# com_board.net
KiCad netlist of a schematic drawn in EAGLE
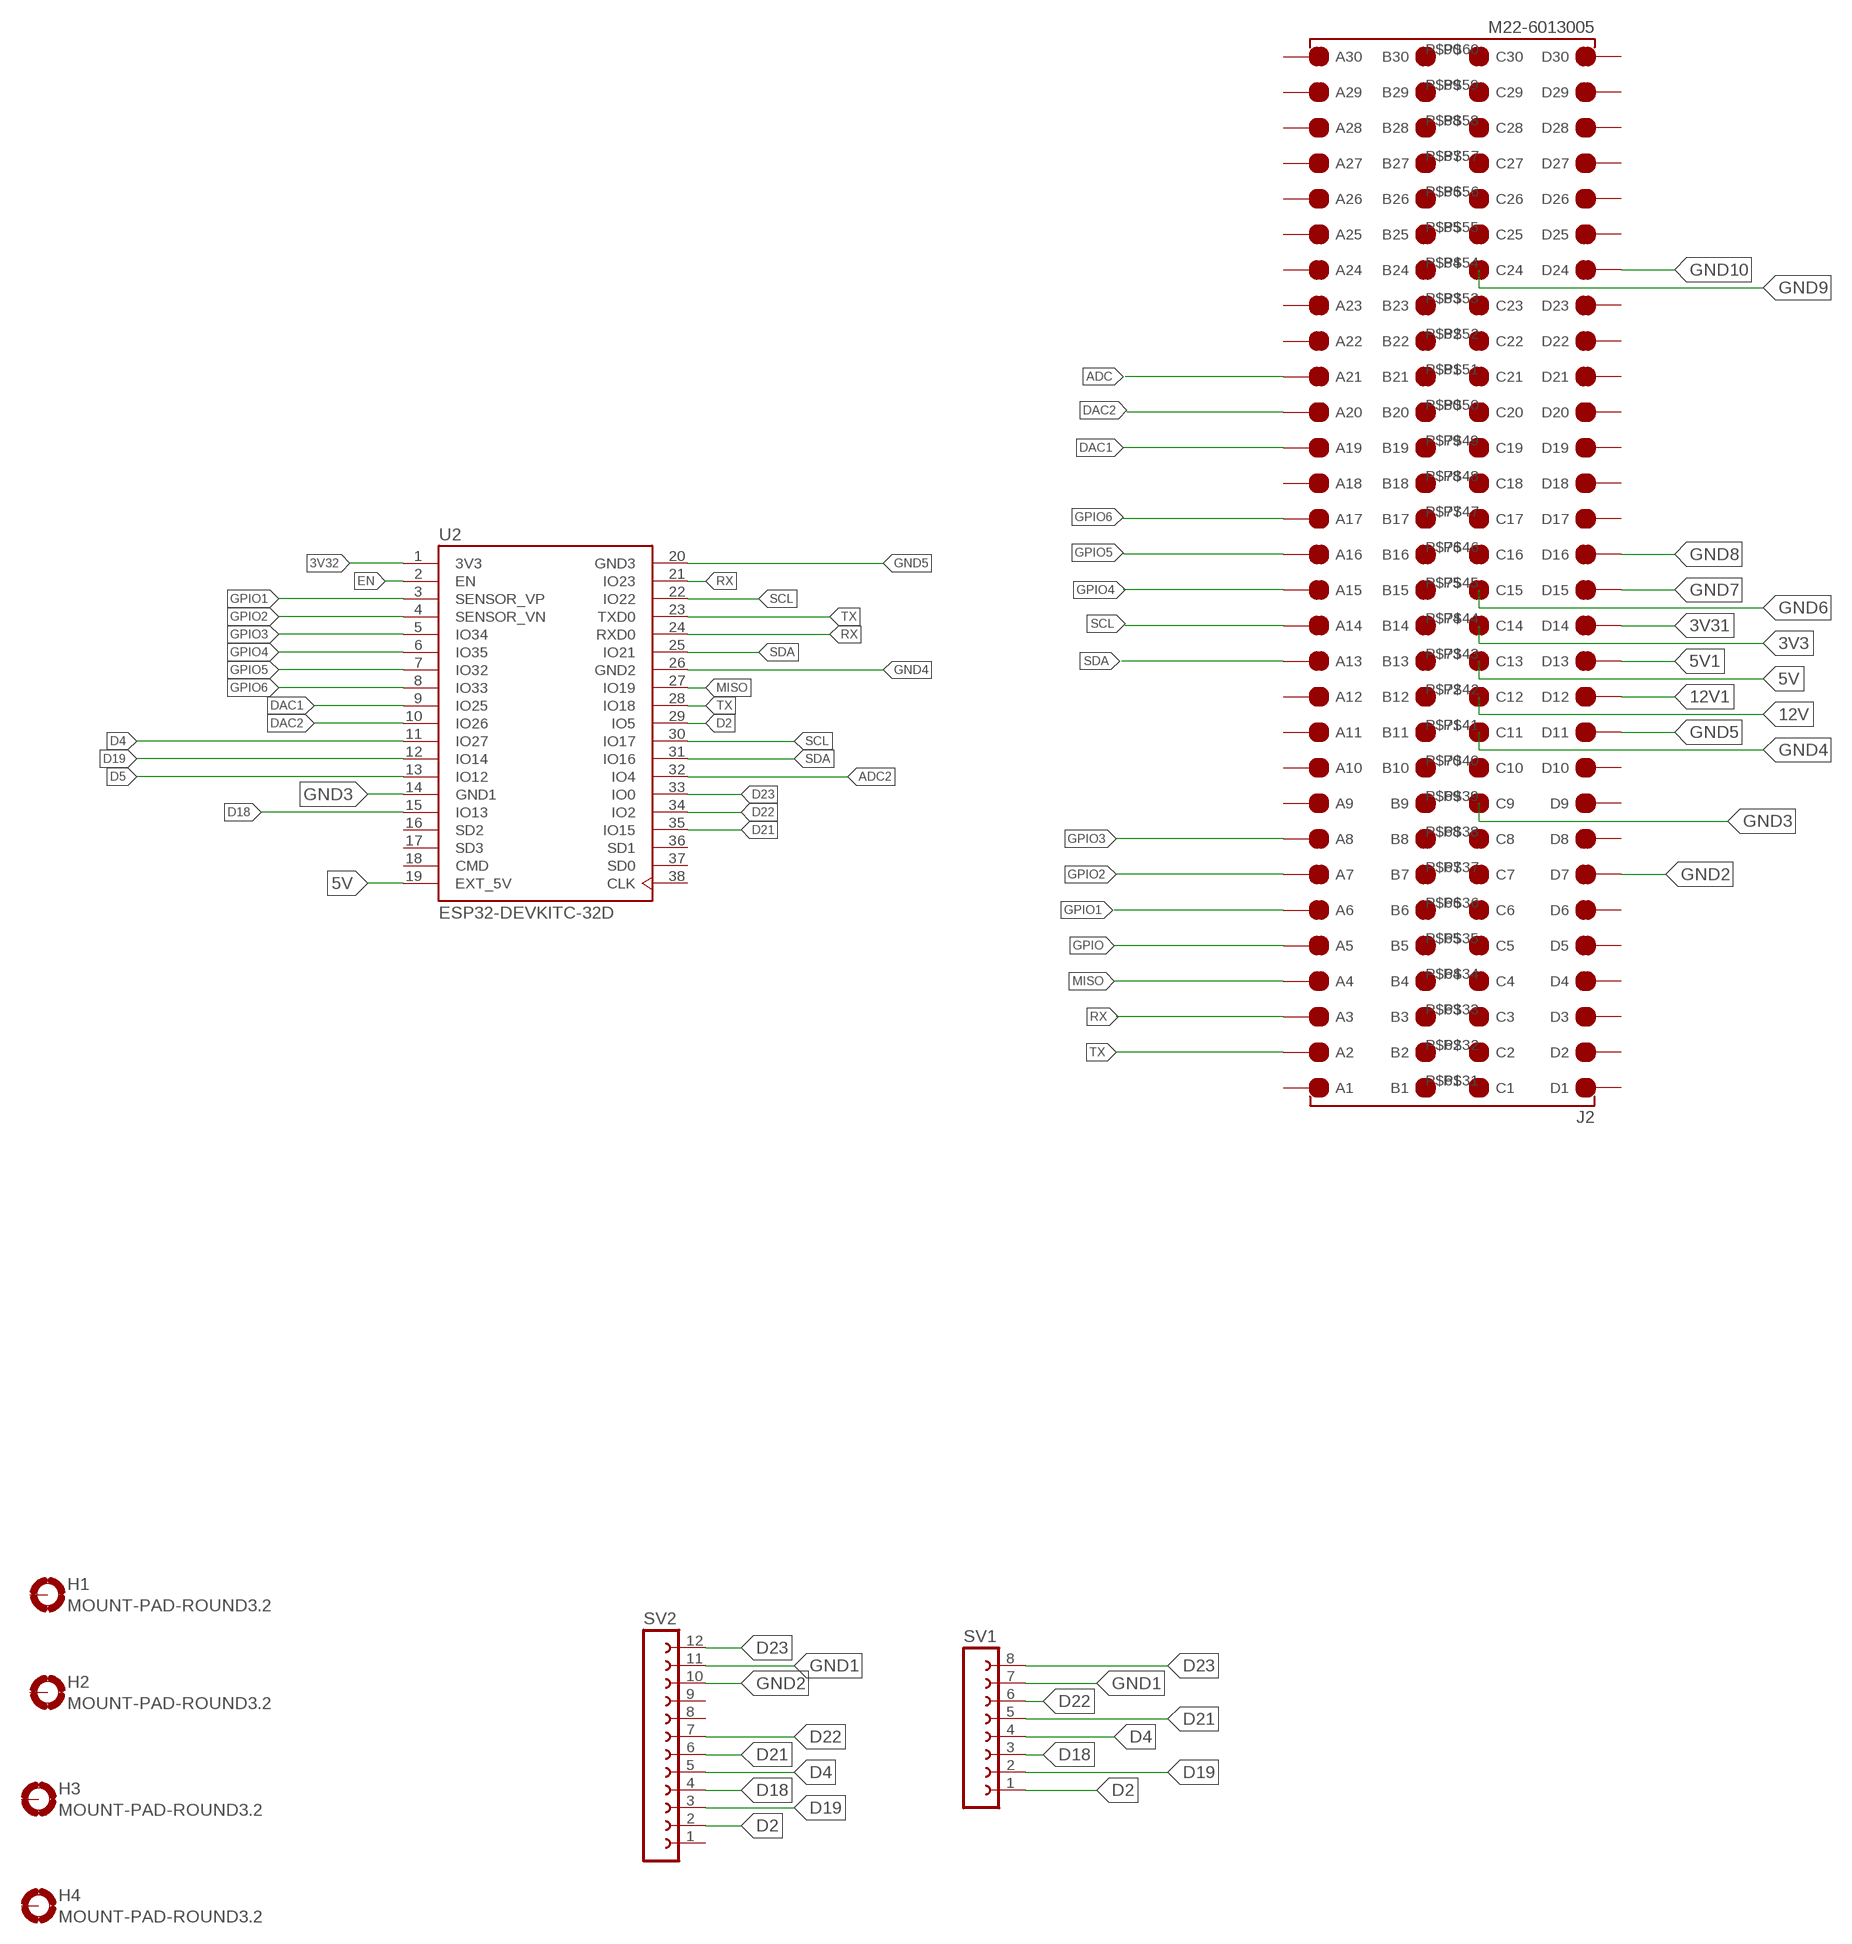
[diagram p0: schematic, sheet 1]

(export (version "E")
  (design (tool "Eeschema 10.0.6"))
  (components
    (comp (ref "H1")
      (value "MOUNT-PAD-ROUND3.2")
      (footprint "eagle-import:3,2-PAD")
      (libsource (lib "eagle-import") (part "MOUNT-PAD-ROUND3.2"))
    )
    (comp (ref "H2")
      (value "MOUNT-PAD-ROUND3.2")
      (footprint "eagle-import:3,2-PAD")
      (libsource (lib "eagle-import") (part "MOUNT-PAD-ROUND3.2"))
    )
    (comp (ref "H3")
      (value "MOUNT-PAD-ROUND3.2")
      (footprint "eagle-import:3,2-PAD")
      (libsource (lib "eagle-import") (part "MOUNT-PAD-ROUND3.2"))
    )
    (comp (ref "H4")
      (value "MOUNT-PAD-ROUND3.2")
      (footprint "eagle-import:3,2-PAD")
      (libsource (lib "eagle-import") (part "MOUNT-PAD-ROUND3.2"))
    )
    (comp (ref "J2")
      (value "M22-6013005")
      (footprint "eagle-import:RHDR120W55P200_4X30_6020X820X9")
      (libsource (lib "eagle-import") (part "M22-6013005"))
    )
    (comp (ref "SV1")
      (value "FE08-1")
      (footprint "eagle-import:FE08")
      (libsource (lib "eagle-import") (part "FE08-1"))
    )
    (comp (ref "SV2")
      (value "FE12-1")
      (footprint "eagle-import:FE12")
      (libsource (lib "eagle-import") (part "FE12-1"))
    )
    (comp (ref "U2")
      (value "ESP32-DEVKITC-32D")
      (footprint "eagle-import:MODULE_ESP32-DEVKITC-32D")
      (fields (field (name "MF") "Espressif Systems"))
      (libsource (lib "eagle-import") (part "ESP32-DEVKITC-32D"))
    )
  )
  (nets
    (net (code "1") (name "3V3") (class "Default")
      (node (ref "J2") (pin "P$44") (pinfunction "C14_P$44") (pintype "passive"))
    )
    (net (code "2") (name "3V31") (class "Default")
      (node (ref "J2") (pin "P$14") (pinfunction "D14_P$14") (pintype "passive"))
    )
    (net (code "3") (name "3V32") (class "Default")
      (node (ref "U2") (pin "1") (pinfunction "3V3_1") (pintype "power_in"))
    )
    (net (code "4") (name "5V") (class "Default")
      (node (ref "J2") (pin "P$43") (pinfunction "C13_P$43") (pintype "passive"))
      (node (ref "U2") (pin "19") (pinfunction "EXT_5V_19") (pintype "power_in"))
    )
    (net (code "5") (name "5V1") (class "Default")
      (node (ref "J2") (pin "P$13") (pinfunction "D13_P$13") (pintype "passive"))
    )
    (net (code "6") (name "12V") (class "Default")
      (node (ref "J2") (pin "P$42") (pinfunction "C12_P$42") (pintype "passive"))
    )
    (net (code "7") (name "12V1") (class "Default")
      (node (ref "J2") (pin "P$12") (pinfunction "D12_P$12") (pintype "passive"))
    )
    (net (code "8") (name "ADC") (class "Default")
      (node (ref "J2") (pin "P$111") (pinfunction "A21_P$111") (pintype "passive"))
    )
    (net (code "9") (name "ADC2") (class "Default")
      (node (ref "U2") (pin "32") (pinfunction "IO4_32") (pintype "bidirectional"))
    )
    (net (code "10") (name "D2") (class "Default")
      (node (ref "SV1") (pin "1") (pinfunction "1_1") (pintype "passive"))
      (node (ref "SV2") (pin "2") (pinfunction "2_2") (pintype "passive"))
      (node (ref "U2") (pin "29") (pinfunction "IO5_29") (pintype "bidirectional"))
    )
    (net (code "11") (name "D4") (class "Default")
      (node (ref "SV1") (pin "4") (pinfunction "4_4") (pintype "passive"))
      (node (ref "SV2") (pin "5") (pinfunction "5_5") (pintype "passive"))
      (node (ref "U2") (pin "11") (pinfunction "IO27_11") (pintype "bidirectional"))
    )
    (net (code "12") (name "D5") (class "Default")
      (node (ref "U2") (pin "13") (pinfunction "IO12_13") (pintype "bidirectional"))
    )
    (net (code "13") (name "D18") (class "Default")
      (node (ref "SV1") (pin "3") (pinfunction "3_3") (pintype "passive"))
      (node (ref "SV2") (pin "4") (pinfunction "4_4") (pintype "passive"))
      (node (ref "U2") (pin "15") (pinfunction "IO13_15") (pintype "bidirectional"))
    )
    (net (code "14") (name "D19") (class "Default")
      (node (ref "SV1") (pin "2") (pinfunction "2_2") (pintype "passive"))
      (node (ref "SV2") (pin "3") (pinfunction "3_3") (pintype "passive"))
      (node (ref "U2") (pin "12") (pinfunction "IO14_12") (pintype "bidirectional"))
    )
    (net (code "15") (name "D21") (class "Default")
      (node (ref "SV1") (pin "5") (pinfunction "5_5") (pintype "passive"))
      (node (ref "SV2") (pin "6") (pinfunction "6_6") (pintype "passive"))
      (node (ref "U2") (pin "35") (pinfunction "IO15_35") (pintype "bidirectional"))
    )
    (net (code "16") (name "D22") (class "Default")
      (node (ref "SV1") (pin "6") (pinfunction "6_6") (pintype "passive"))
      (node (ref "SV2") (pin "7") (pinfunction "7_7") (pintype "passive"))
      (node (ref "U2") (pin "34") (pinfunction "IO2_34") (pintype "bidirectional"))
    )
    (net (code "17") (name "D23") (class "Default")
      (node (ref "SV1") (pin "8") (pinfunction "8_8") (pintype "passive"))
      (node (ref "SV2") (pin "12") (pinfunction "12_12") (pintype "passive"))
      (node (ref "U2") (pin "33") (pinfunction "IO0_33") (pintype "bidirectional"))
    )
    (net (code "18") (name "DAC1") (class "Default")
      (node (ref "J2") (pin "P$109") (pinfunction "A19_P$109") (pintype "passive"))
      (node (ref "U2") (pin "9") (pinfunction "IO25_9") (pintype "bidirectional"))
    )
    (net (code "19") (name "DAC2") (class "Default")
      (node (ref "J2") (pin "P$110") (pinfunction "A20_P$110") (pintype "passive"))
      (node (ref "U2") (pin "10") (pinfunction "IO26_10") (pintype "bidirectional"))
    )
    (net (code "20") (name "EN") (class "Default")
      (node (ref "U2") (pin "2") (pinfunction "EN_2") (pintype "input"))
    )
    (net (code "21") (name "GND1") (class "Default")
      (node (ref "SV1") (pin "7") (pinfunction "7_7") (pintype "passive"))
      (node (ref "SV2") (pin "11") (pinfunction "11_11") (pintype "passive"))
    )
    (net (code "22") (name "GND2") (class "Default")
      (node (ref "J2") (pin "P$7") (pinfunction "D7_P$7") (pintype "passive"))
      (node (ref "SV2") (pin "10") (pinfunction "10_10") (pintype "passive"))
    )
    (net (code "23") (name "GND3") (class "Default")
      (node (ref "J2") (pin "P$39") (pinfunction "C9_P$39") (pintype "passive"))
      (node (ref "U2") (pin "14") (pinfunction "GND1_14") (pintype "power_in"))
    )
    (net (code "24") (name "GND4") (class "Default")
      (node (ref "J2") (pin "P$41") (pinfunction "C11_P$41") (pintype "passive"))
      (node (ref "U2") (pin "26") (pinfunction "GND2_26") (pintype "power_in"))
    )
    (net (code "25") (name "GND5") (class "Default")
      (node (ref "J2") (pin "P$11") (pinfunction "D11_P$11") (pintype "passive"))
      (node (ref "U2") (pin "20") (pinfunction "GND3_20") (pintype "power_in"))
    )
    (net (code "26") (name "GND6") (class "Default")
      (node (ref "J2") (pin "P$45") (pinfunction "C15_P$45") (pintype "passive"))
    )
    (net (code "27") (name "GND7") (class "Default")
      (node (ref "J2") (pin "P$15") (pinfunction "D15_P$15") (pintype "passive"))
    )
    (net (code "28") (name "GND8") (class "Default")
      (node (ref "J2") (pin "P$16") (pinfunction "D16_P$16") (pintype "passive"))
    )
    (net (code "29") (name "GND9") (class "Default")
      (node (ref "J2") (pin "P$54") (pinfunction "C24_P$54") (pintype "passive"))
    )
    (net (code "30") (name "GND10") (class "Default")
      (node (ref "J2") (pin "P$24") (pinfunction "D24_P$24") (pintype "passive"))
    )
    (net (code "31") (name "GPIO") (class "Default")
      (node (ref "J2") (pin "P$95") (pinfunction "A5_P$95") (pintype "passive"))
    )
    (net (code "32") (name "GPIO1") (class "Default")
      (node (ref "J2") (pin "P$96") (pinfunction "A6_P$96") (pintype "passive"))
      (node (ref "U2") (pin "3") (pinfunction "SENSOR_VP_3") (pintype "input"))
    )
    (net (code "33") (name "GPIO2") (class "Default")
      (node (ref "J2") (pin "P$97") (pinfunction "A7_P$97") (pintype "passive"))
      (node (ref "U2") (pin "4") (pinfunction "SENSOR_VN_4") (pintype "input"))
    )
    (net (code "34") (name "GPIO3") (class "Default")
      (node (ref "J2") (pin "P$98") (pinfunction "A8_P$98") (pintype "passive"))
      (node (ref "U2") (pin "5") (pinfunction "IO34_5") (pintype "bidirectional"))
    )
    (net (code "35") (name "GPIO4") (class "Default")
      (node (ref "J2") (pin "P$105") (pinfunction "A15_P$105") (pintype "passive"))
      (node (ref "U2") (pin "6") (pinfunction "IO35_6") (pintype "bidirectional"))
    )
    (net (code "36") (name "GPIO5") (class "Default")
      (node (ref "J2") (pin "P$106") (pinfunction "A16_P$106") (pintype "passive"))
      (node (ref "U2") (pin "7") (pinfunction "IO32_7") (pintype "bidirectional"))
    )
    (net (code "37") (name "GPIO6") (class "Default")
      (node (ref "J2") (pin "P$107") (pinfunction "A17_P$107") (pintype "passive"))
      (node (ref "U2") (pin "8") (pinfunction "IO33_8") (pintype "bidirectional"))
    )
    (net (code "38") (name "MISO") (class "Default")
      (node (ref "J2") (pin "P$94") (pinfunction "A4_P$94") (pintype "passive"))
      (node (ref "U2") (pin "27") (pinfunction "IO19_27") (pintype "bidirectional"))
    )
    (net (code "39") (name "RX") (class "Default")
      (node (ref "J2") (pin "P$93") (pinfunction "A3_P$93") (pintype "passive"))
      (node (ref "U2") (pin "21") (pinfunction "IO23_21") (pintype "bidirectional"))
      (node (ref "U2") (pin "24") (pinfunction "RXD0_24") (pintype "input"))
    )
    (net (code "40") (name "SCL") (class "Default")
      (node (ref "J2") (pin "P$104") (pinfunction "A14_P$104") (pintype "passive"))
      (node (ref "U2") (pin "22") (pinfunction "IO22_22") (pintype "bidirectional"))
      (node (ref "U2") (pin "30") (pinfunction "IO17_30") (pintype "bidirectional"))
    )
    (net (code "41") (name "SDA") (class "Default")
      (node (ref "J2") (pin "P$103") (pinfunction "A13_P$103") (pintype "passive"))
      (node (ref "U2") (pin "25") (pinfunction "IO21_25") (pintype "bidirectional"))
      (node (ref "U2") (pin "31") (pinfunction "IO16_31") (pintype "bidirectional"))
    )
    (net (code "42") (name "TX") (class "Default")
      (node (ref "J2") (pin "P$92") (pinfunction "A2_P$92") (pintype "passive"))
      (node (ref "U2") (pin "23") (pinfunction "TXD0_23") (pintype "output"))
      (node (ref "U2") (pin "28") (pinfunction "IO18_28") (pintype "bidirectional"))
    )
    (net (code "43") (name "unconnected-(H1-MOUNT-PadB3,2)") (class "Default")
      (node (ref "H1") (pin "B3,2") (pinfunction "MOUNT_B3,2") (pintype "passive"))
    )
    (net (code "44") (name "unconnected-(H2-MOUNT-PadB3,2)") (class "Default")
      (node (ref "H2") (pin "B3,2") (pinfunction "MOUNT_B3,2") (pintype "passive"))
    )
    (net (code "45") (name "unconnected-(H3-MOUNT-PadB3,2)") (class "Default")
      (node (ref "H3") (pin "B3,2") (pinfunction "MOUNT_B3,2") (pintype "passive"))
    )
    (net (code "46") (name "unconnected-(H4-MOUNT-PadB3,2)") (class "Default")
      (node (ref "H4") (pin "B3,2") (pinfunction "MOUNT_B3,2") (pintype "passive"))
    )
    (net (code "47") (name "unconnected-(J2-A1-PadP$91)") (class "Default")
      (node (ref "J2") (pin "P$91") (pinfunction "A1_P$91") (pintype "passive"))
    )
    (net (code "48") (name "unconnected-(J2-A9-PadP$99)") (class "Default")
      (node (ref "J2") (pin "P$99") (pinfunction "A9_P$99") (pintype "passive"))
    )
    (net (code "49") (name "unconnected-(J2-A10-PadP$100)") (class "Default")
      (node (ref "J2") (pin "P$100") (pinfunction "A10_P$100") (pintype "passive"))
    )
    (net (code "50") (name "unconnected-(J2-A11-PadP$101)") (class "Default")
      (node (ref "J2") (pin "P$101") (pinfunction "A11_P$101") (pintype "passive"))
    )
    (net (code "51") (name "unconnected-(J2-A12-PadP$102)") (class "Default")
      (node (ref "J2") (pin "P$102") (pinfunction "A12_P$102") (pintype "passive"))
    )
    (net (code "52") (name "unconnected-(J2-A18-PadP$108)") (class "Default")
      (node (ref "J2") (pin "P$108") (pinfunction "A18_P$108") (pintype "passive"))
    )
    (net (code "53") (name "unconnected-(J2-A22-PadP$112)") (class "Default")
      (node (ref "J2") (pin "P$112") (pinfunction "A22_P$112") (pintype "passive"))
    )
    (net (code "54") (name "unconnected-(J2-A23-PadP$113)") (class "Default")
      (node (ref "J2") (pin "P$113") (pinfunction "A23_P$113") (pintype "passive"))
    )
    (net (code "55") (name "unconnected-(J2-A24-PadP$114)") (class "Default")
      (node (ref "J2") (pin "P$114") (pinfunction "A24_P$114") (pintype "passive"))
    )
    (net (code "56") (name "unconnected-(J2-A25-PadP$115)") (class "Default")
      (node (ref "J2") (pin "P$115") (pinfunction "A25_P$115") (pintype "passive"))
    )
    (net (code "57") (name "unconnected-(J2-A26-PadP$116)") (class "Default")
      (node (ref "J2") (pin "P$116") (pinfunction "A26_P$116") (pintype "passive"))
    )
    (net (code "58") (name "unconnected-(J2-A27-PadP$117)") (class "Default")
      (node (ref "J2") (pin "P$117") (pinfunction "A27_P$117") (pintype "passive"))
    )
    (net (code "59") (name "unconnected-(J2-A28-PadP$118)") (class "Default")
      (node (ref "J2") (pin "P$118") (pinfunction "A28_P$118") (pintype "passive"))
    )
    (net (code "60") (name "unconnected-(J2-A29-PadP$119)") (class "Default")
      (node (ref "J2") (pin "P$119") (pinfunction "A29_P$119") (pintype "passive"))
    )
    (net (code "61") (name "unconnected-(J2-A30-PadP$120)") (class "Default")
      (node (ref "J2") (pin "P$120") (pinfunction "A30_P$120") (pintype "passive"))
    )
    (net (code "62") (name "unconnected-(J2-B1-PadP$61)") (class "Default")
      (node (ref "J2") (pin "P$61") (pinfunction "B1_P$61") (pintype "passive"))
    )
    (net (code "63") (name "unconnected-(J2-B2-PadP$62)") (class "Default")
      (node (ref "J2") (pin "P$62") (pinfunction "B2_P$62") (pintype "passive"))
    )
    (net (code "64") (name "unconnected-(J2-B3-PadP$63)") (class "Default")
      (node (ref "J2") (pin "P$63") (pinfunction "B3_P$63") (pintype "passive"))
    )
    (net (code "65") (name "unconnected-(J2-B4-PadP$64)") (class "Default")
      (node (ref "J2") (pin "P$64") (pinfunction "B4_P$64") (pintype "passive"))
    )
    (net (code "66") (name "unconnected-(J2-B5-PadP$65)") (class "Default")
      (node (ref "J2") (pin "P$65") (pinfunction "B5_P$65") (pintype "passive"))
    )
    (net (code "67") (name "unconnected-(J2-B6-PadP$66)") (class "Default")
      (node (ref "J2") (pin "P$66") (pinfunction "B6_P$66") (pintype "passive"))
    )
    (net (code "68") (name "unconnected-(J2-B7-PadP$67)") (class "Default")
      (node (ref "J2") (pin "P$67") (pinfunction "B7_P$67") (pintype "passive"))
    )
    (net (code "69") (name "unconnected-(J2-B8-PadP$68)") (class "Default")
      (node (ref "J2") (pin "P$68") (pinfunction "B8_P$68") (pintype "passive"))
    )
    (net (code "70") (name "unconnected-(J2-B9-PadP$69)") (class "Default")
      (node (ref "J2") (pin "P$69") (pinfunction "B9_P$69") (pintype "passive"))
    )
    (net (code "71") (name "unconnected-(J2-B10-PadP$70)") (class "Default")
      (node (ref "J2") (pin "P$70") (pinfunction "B10_P$70") (pintype "passive"))
    )
    (net (code "72") (name "unconnected-(J2-B11-PadP$71)") (class "Default")
      (node (ref "J2") (pin "P$71") (pinfunction "B11_P$71") (pintype "passive"))
    )
    (net (code "73") (name "unconnected-(J2-B12-PadP$72)") (class "Default")
      (node (ref "J2") (pin "P$72") (pinfunction "B12_P$72") (pintype "passive"))
    )
    (net (code "74") (name "unconnected-(J2-B13-PadP$73)") (class "Default")
      (node (ref "J2") (pin "P$73") (pinfunction "B13_P$73") (pintype "passive"))
    )
    (net (code "75") (name "unconnected-(J2-B14-PadP$74)") (class "Default")
      (node (ref "J2") (pin "P$74") (pinfunction "B14_P$74") (pintype "passive"))
    )
    (net (code "76") (name "unconnected-(J2-B15-PadP$75)") (class "Default")
      (node (ref "J2") (pin "P$75") (pinfunction "B15_P$75") (pintype "passive"))
    )
    (net (code "77") (name "unconnected-(J2-B16-PadP$76)") (class "Default")
      (node (ref "J2") (pin "P$76") (pinfunction "B16_P$76") (pintype "passive"))
    )
    (net (code "78") (name "unconnected-(J2-B17-PadP$77)") (class "Default")
      (node (ref "J2") (pin "P$77") (pinfunction "B17_P$77") (pintype "passive"))
    )
    (net (code "79") (name "unconnected-(J2-B18-PadP$78)") (class "Default")
      (node (ref "J2") (pin "P$78") (pinfunction "B18_P$78") (pintype "passive"))
    )
    (net (code "80") (name "unconnected-(J2-B19-PadP$79)") (class "Default")
      (node (ref "J2") (pin "P$79") (pinfunction "B19_P$79") (pintype "passive"))
    )
    (net (code "81") (name "unconnected-(J2-B20-PadP$80)") (class "Default")
      (node (ref "J2") (pin "P$80") (pinfunction "B20_P$80") (pintype "passive"))
    )
    (net (code "82") (name "unconnected-(J2-B21-PadP$81)") (class "Default")
      (node (ref "J2") (pin "P$81") (pinfunction "B21_P$81") (pintype "passive"))
    )
    (net (code "83") (name "unconnected-(J2-B22-PadP$82)") (class "Default")
      (node (ref "J2") (pin "P$82") (pinfunction "B22_P$82") (pintype "passive"))
    )
    (net (code "84") (name "unconnected-(J2-B23-PadP$83)") (class "Default")
      (node (ref "J2") (pin "P$83") (pinfunction "B23_P$83") (pintype "passive"))
    )
    (net (code "85") (name "unconnected-(J2-B24-PadP$84)") (class "Default")
      (node (ref "J2") (pin "P$84") (pinfunction "B24_P$84") (pintype "passive"))
    )
    (net (code "86") (name "unconnected-(J2-B25-PadP$85)") (class "Default")
      (node (ref "J2") (pin "P$85") (pinfunction "B25_P$85") (pintype "passive"))
    )
    (net (code "87") (name "unconnected-(J2-B26-PadP$86)") (class "Default")
      (node (ref "J2") (pin "P$86") (pinfunction "B26_P$86") (pintype "passive"))
    )
    (net (code "88") (name "unconnected-(J2-B27-PadP$87)") (class "Default")
      (node (ref "J2") (pin "P$87") (pinfunction "B27_P$87") (pintype "passive"))
    )
    (net (code "89") (name "unconnected-(J2-B28-PadP$88)") (class "Default")
      (node (ref "J2") (pin "P$88") (pinfunction "B28_P$88") (pintype "passive"))
    )
    (net (code "90") (name "unconnected-(J2-B29-PadP$89)") (class "Default")
      (node (ref "J2") (pin "P$89") (pinfunction "B29_P$89") (pintype "passive"))
    )
    (net (code "91") (name "unconnected-(J2-B30-PadP$90)") (class "Default")
      (node (ref "J2") (pin "P$90") (pinfunction "B30_P$90") (pintype "passive"))
    )
    (net (code "92") (name "unconnected-(J2-C1-PadP$31)") (class "Default")
      (node (ref "J2") (pin "P$31") (pinfunction "C1_P$31") (pintype "passive"))
    )
    (net (code "93") (name "unconnected-(J2-C2-PadP$32)") (class "Default")
      (node (ref "J2") (pin "P$32") (pinfunction "C2_P$32") (pintype "passive"))
    )
    (net (code "94") (name "unconnected-(J2-C3-PadP$33)") (class "Default")
      (node (ref "J2") (pin "P$33") (pinfunction "C3_P$33") (pintype "passive"))
    )
    (net (code "95") (name "unconnected-(J2-C4-PadP$34)") (class "Default")
      (node (ref "J2") (pin "P$34") (pinfunction "C4_P$34") (pintype "passive"))
    )
    (net (code "96") (name "unconnected-(J2-C5-PadP$35)") (class "Default")
      (node (ref "J2") (pin "P$35") (pinfunction "C5_P$35") (pintype "passive"))
    )
    (net (code "97") (name "unconnected-(J2-C6-PadP$36)") (class "Default")
      (node (ref "J2") (pin "P$36") (pinfunction "C6_P$36") (pintype "passive"))
    )
    (net (code "98") (name "unconnected-(J2-C7-PadP$37)") (class "Default")
      (node (ref "J2") (pin "P$37") (pinfunction "C7_P$37") (pintype "passive"))
    )
    (net (code "99") (name "unconnected-(J2-C8-PadP$38)") (class "Default")
      (node (ref "J2") (pin "P$38") (pinfunction "C8_P$38") (pintype "passive"))
    )
    (net (code "100") (name "unconnected-(J2-C10-PadP$40)") (class "Default")
      (node (ref "J2") (pin "P$40") (pinfunction "C10_P$40") (pintype "passive"))
    )
    (net (code "101") (name "unconnected-(J2-C16-PadP$46)") (class "Default")
      (node (ref "J2") (pin "P$46") (pinfunction "C16_P$46") (pintype "passive"))
    )
    (net (code "102") (name "unconnected-(J2-C17-PadP$47)") (class "Default")
      (node (ref "J2") (pin "P$47") (pinfunction "C17_P$47") (pintype "passive"))
    )
    (net (code "103") (name "unconnected-(J2-C18-PadP$48)") (class "Default")
      (node (ref "J2") (pin "P$48") (pinfunction "C18_P$48") (pintype "passive"))
    )
    (net (code "104") (name "unconnected-(J2-C19-PadP$49)") (class "Default")
      (node (ref "J2") (pin "P$49") (pinfunction "C19_P$49") (pintype "passive"))
    )
    (net (code "105") (name "unconnected-(J2-C20-PadP$50)") (class "Default")
      (node (ref "J2") (pin "P$50") (pinfunction "C20_P$50") (pintype "passive"))
    )
    (net (code "106") (name "unconnected-(J2-C21-PadP$51)") (class "Default")
      (node (ref "J2") (pin "P$51") (pinfunction "C21_P$51") (pintype "passive"))
    )
    (net (code "107") (name "unconnected-(J2-C22-PadP$52)") (class "Default")
      (node (ref "J2") (pin "P$52") (pinfunction "C22_P$52") (pintype "passive"))
    )
    (net (code "108") (name "unconnected-(J2-C23-PadP$53)") (class "Default")
      (node (ref "J2") (pin "P$53") (pinfunction "C23_P$53") (pintype "passive"))
    )
    (net (code "109") (name "unconnected-(J2-C25-PadP$55)") (class "Default")
      (node (ref "J2") (pin "P$55") (pinfunction "C25_P$55") (pintype "passive"))
    )
    (net (code "110") (name "unconnected-(J2-C26-PadP$56)") (class "Default")
      (node (ref "J2") (pin "P$56") (pinfunction "C26_P$56") (pintype "passive"))
    )
    (net (code "111") (name "unconnected-(J2-C27-PadP$57)") (class "Default")
      (node (ref "J2") (pin "P$57") (pinfunction "C27_P$57") (pintype "passive"))
    )
    (net (code "112") (name "unconnected-(J2-C28-PadP$58)") (class "Default")
      (node (ref "J2") (pin "P$58") (pinfunction "C28_P$58") (pintype "passive"))
    )
    (net (code "113") (name "unconnected-(J2-C29-PadP$59)") (class "Default")
      (node (ref "J2") (pin "P$59") (pinfunction "C29_P$59") (pintype "passive"))
    )
    (net (code "114") (name "unconnected-(J2-C30-PadP$60)") (class "Default")
      (node (ref "J2") (pin "P$60") (pinfunction "C30_P$60") (pintype "passive"))
    )
    (net (code "115") (name "unconnected-(J2-D1-PadP$1)") (class "Default")
      (node (ref "J2") (pin "P$1") (pinfunction "D1_P$1") (pintype "passive"))
    )
    (net (code "116") (name "unconnected-(J2-D2-PadP$2)") (class "Default")
      (node (ref "J2") (pin "P$2") (pinfunction "D2_P$2") (pintype "passive"))
    )
    (net (code "117") (name "unconnected-(J2-D3-PadP$3)") (class "Default")
      (node (ref "J2") (pin "P$3") (pinfunction "D3_P$3") (pintype "passive"))
    )
    (net (code "118") (name "unconnected-(J2-D4-PadP$4)") (class "Default")
      (node (ref "J2") (pin "P$4") (pinfunction "D4_P$4") (pintype "passive"))
    )
    (net (code "119") (name "unconnected-(J2-D5-PadP$5)") (class "Default")
      (node (ref "J2") (pin "P$5") (pinfunction "D5_P$5") (pintype "passive"))
    )
    (net (code "120") (name "unconnected-(J2-D6-PadP$6)") (class "Default")
      (node (ref "J2") (pin "P$6") (pinfunction "D6_P$6") (pintype "passive"))
    )
    (net (code "121") (name "unconnected-(J2-D8-PadP$8)") (class "Default")
      (node (ref "J2") (pin "P$8") (pinfunction "D8_P$8") (pintype "passive"))
    )
    (net (code "122") (name "unconnected-(J2-D9-PadP$9)") (class "Default")
      (node (ref "J2") (pin "P$9") (pinfunction "D9_P$9") (pintype "passive"))
    )
    (net (code "123") (name "unconnected-(J2-D10-PadP$10)") (class "Default")
      (node (ref "J2") (pin "P$10") (pinfunction "D10_P$10") (pintype "passive"))
    )
    (net (code "124") (name "unconnected-(J2-D17-PadP$17)") (class "Default")
      (node (ref "J2") (pin "P$17") (pinfunction "D17_P$17") (pintype "passive"))
    )
    (net (code "125") (name "unconnected-(J2-D18-PadP$18)") (class "Default")
      (node (ref "J2") (pin "P$18") (pinfunction "D18_P$18") (pintype "passive"))
    )
    (net (code "126") (name "unconnected-(J2-D19-PadP$19)") (class "Default")
      (node (ref "J2") (pin "P$19") (pinfunction "D19_P$19") (pintype "passive"))
    )
    (net (code "127") (name "unconnected-(J2-D20-PadP$20)") (class "Default")
      (node (ref "J2") (pin "P$20") (pinfunction "D20_P$20") (pintype "passive"))
    )
    (net (code "128") (name "unconnected-(J2-D21-PadP$21)") (class "Default")
      (node (ref "J2") (pin "P$21") (pinfunction "D21_P$21") (pintype "passive"))
    )
    (net (code "129") (name "unconnected-(J2-D22-PadP$22)") (class "Default")
      (node (ref "J2") (pin "P$22") (pinfunction "D22_P$22") (pintype "passive"))
    )
    (net (code "130") (name "unconnected-(J2-D23-PadP$23)") (class "Default")
      (node (ref "J2") (pin "P$23") (pinfunction "D23_P$23") (pintype "passive"))
    )
    (net (code "131") (name "unconnected-(J2-D25-PadP$25)") (class "Default")
      (node (ref "J2") (pin "P$25") (pinfunction "D25_P$25") (pintype "passive"))
    )
    (net (code "132") (name "unconnected-(J2-D26-PadP$26)") (class "Default")
      (node (ref "J2") (pin "P$26") (pinfunction "D26_P$26") (pintype "passive"))
    )
    (net (code "133") (name "unconnected-(J2-D27-PadP$27)") (class "Default")
      (node (ref "J2") (pin "P$27") (pinfunction "D27_P$27") (pintype "passive"))
    )
    (net (code "134") (name "unconnected-(J2-D28-PadP$28)") (class "Default")
      (node (ref "J2") (pin "P$28") (pinfunction "D28_P$28") (pintype "passive"))
    )
    (net (code "135") (name "unconnected-(J2-D29-PadP$29)") (class "Default")
      (node (ref "J2") (pin "P$29") (pinfunction "D29_P$29") (pintype "passive"))
    )
    (net (code "136") (name "unconnected-(J2-D30-PadP$30)") (class "Default")
      (node (ref "J2") (pin "P$30") (pinfunction "D30_P$30") (pintype "passive"))
    )
    (net (code "137") (name "unconnected-(SV2-Pad1)") (class "Default")
      (node (ref "SV2") (pin "1") (pinfunction "1_1") (pintype "passive"))
    )
    (net (code "138") (name "unconnected-(SV2-Pad8)") (class "Default")
      (node (ref "SV2") (pin "8") (pinfunction "8_8") (pintype "passive"))
    )
    (net (code "139") (name "unconnected-(SV2-Pad9)") (class "Default")
      (node (ref "SV2") (pin "9") (pinfunction "9_9") (pintype "passive"))
    )
    (net (code "140") (name "unconnected-(U2-CLK-Pad38)") (class "Default")
      (node (ref "U2") (pin "38") (pinfunction "CLK_38") (pintype "input"))
    )
    (net (code "141") (name "unconnected-(U2-CMD-Pad18)") (class "Default")
      (node (ref "U2") (pin "18") (pinfunction "CMD_18") (pintype "bidirectional"))
    )
    (net (code "142") (name "unconnected-(U2-SD0-Pad37)") (class "Default")
      (node (ref "U2") (pin "37") (pinfunction "SD0_37") (pintype "bidirectional"))
    )
    (net (code "143") (name "unconnected-(U2-SD1-Pad36)") (class "Default")
      (node (ref "U2") (pin "36") (pinfunction "SD1_36") (pintype "bidirectional"))
    )
    (net (code "144") (name "unconnected-(U2-SD2-Pad16)") (class "Default")
      (node (ref "U2") (pin "16") (pinfunction "SD2_16") (pintype "bidirectional"))
    )
    (net (code "145") (name "unconnected-(U2-SD3-Pad17)") (class "Default")
      (node (ref "U2") (pin "17") (pinfunction "SD3_17") (pintype "bidirectional"))
    )
  )
)
